# pam2803-boost-driver-17mm-mk-1_1.net
KiCad netlist of a schematic drawn in EAGLE
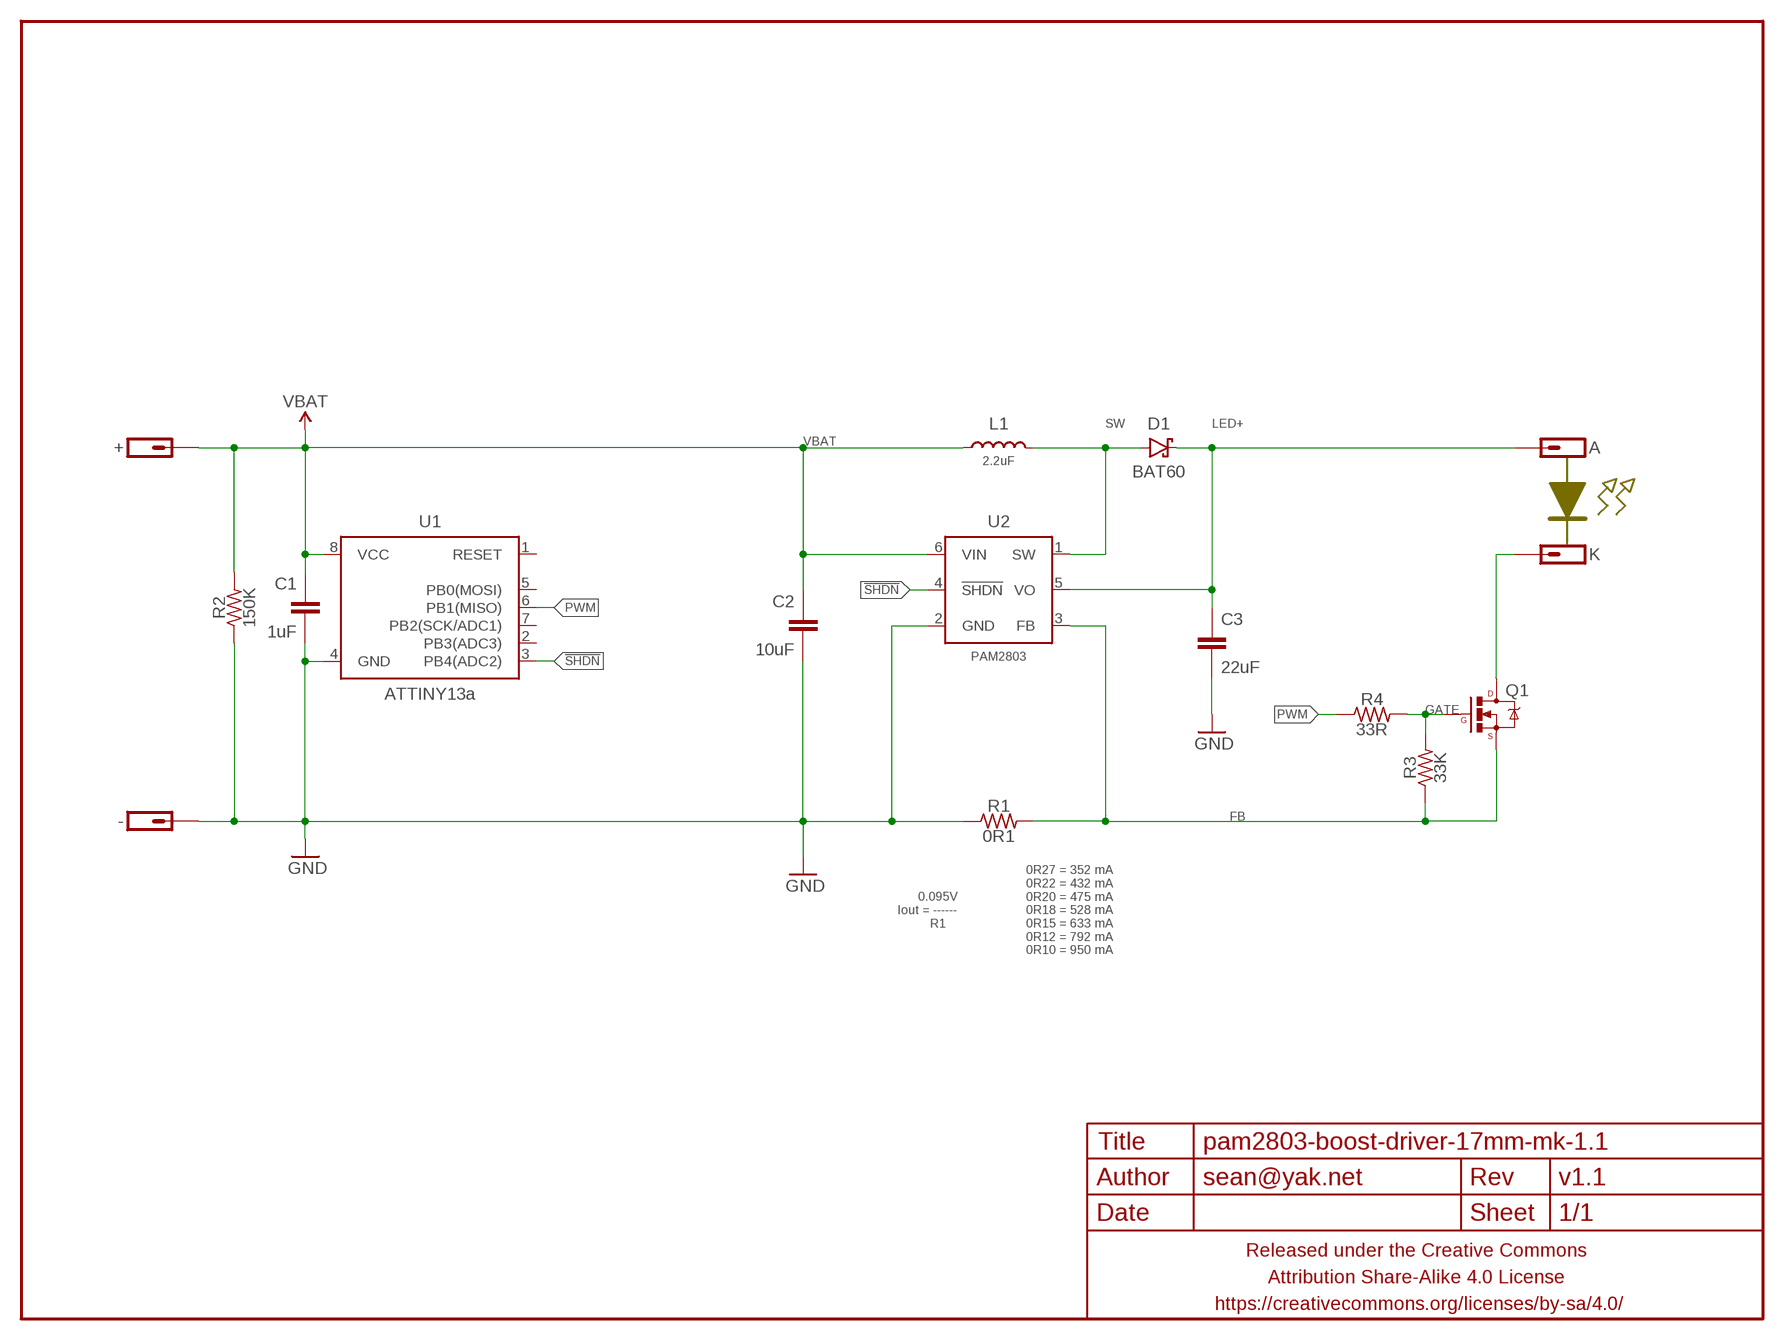
[diagram p0: schematic, sheet 1]

(export (version "E")
  (design (tool "Eeschema 10.0.6"))
  (components
    (comp (ref "+")
      (value "M01PTH-1MM-CIR-NS")
      (footprint "eagle-import:1X01-1MM-CIR-NS")
      (libsource (lib "eagle-import") (part "M01PTH-1MM-CIR-NS"))
    )
    (comp (ref "-")
      (value "M01NOT-A-VIA-NOPE")
      (footprint "eagle-import:1X01_NOSILK_NOSTOP")
      (libsource (lib "eagle-import") (part "M01NOT-A-VIA-NOPE"))
    )
    (comp (ref "A")
      (value "M01PTH-1MM-CIR-NS")
      (footprint "eagle-import:1X01-1MM-CIR-NS")
      (libsource (lib "eagle-import") (part "M01PTH-1MM-CIR-NS"))
    )
    (comp (ref "C1")
      (value "1uF")
      (footprint "eagle-import:C0402")
      (libsource (lib "eagle-import") (part "CAPACITOR-CERAMICC0402"))
    )
    (comp (ref "C2")
      (value "10uF")
      (footprint "eagle-import:C0805-TIGHTER")
      (libsource (lib "eagle-import") (part "CAPACITOR-CERAMICC0805-TIGHTER"))
    )
    (comp (ref "C3")
      (value "22uF")
      (footprint "eagle-import:C0805-TIGHTER")
      (libsource (lib "eagle-import") (part "CAPACITOR-CERAMICC0805-TIGHTER"))
    )
    (comp (ref "D1")
      (value "BAT60")
      (footprint "eagle-import:SOD323-SCHOTTKY")
      (libsource (lib "eagle-import") (part "DIODE-SCHOTTKYSOD323"))
    )
    (comp (ref "FRAME1")
      (value "FRAME-LETTERNO_PACKAGE")
      (footprint "eagle-import:DUMMY")
      (fields (field (name "DESIGNER") "sean@yak.net") (field (name "VERSION") "v1.1"))
      (libsource (lib "eagle-import") (part "FRAME-LETTERNO_PACKAGE"))
    )
    (comp (ref "K")
      (value "M01PTH-1MM-CIR-NS")
      (footprint "eagle-import:1X01-1MM-CIR-NS")
      (libsource (lib "eagle-import") (part "M01PTH-1MM-CIR-NS"))
    )
    (comp (ref "L1")
      (value "2.2uF")
      (footprint "eagle-import:XFL4020")
      (libsource (lib "eagle-import") (part "INDUCTORXFL4020"))
    )
    (comp (ref "Q1")
      (value "MOSFET-NCHANNELIRLML2502")
      (footprint "eagle-import:SOT23")
      (libsource (lib "eagle-import") (part "MOSFET-NCHANNELIRLML2502"))
    )
    (comp (ref "R1")
      (value "0R1")
      (footprint "eagle-import:R0805-TIGHTER")
      (libsource (lib "eagle-import") (part "RESISTORR0805-TIGHTER"))
    )
    (comp (ref "R2")
      (value "150K")
      (footprint "eagle-import:R0603-TIGHTER")
      (libsource (lib "eagle-import") (part "RESISTORR0603-TIGHTER"))
    )
    (comp (ref "R3")
      (value "33K")
      (footprint "eagle-import:R0603-TIGHTER")
      (libsource (lib "eagle-import") (part "RESISTORR0603-TIGHTER"))
    )
    (comp (ref "R4")
      (value "33R")
      (footprint "eagle-import:R0603-TIGHTER")
      (libsource (lib "eagle-import") (part "RESISTORR0603-TIGHTER"))
    )
    (comp (ref "U1")
      (value "ATTINY13a")
      (footprint "eagle-import:SO08-SKINNYPADS")
      (libsource (lib "eagle-import") (part "ATTINY13SOIC-NARROWER"))
    )
    (comp (ref "U2")
      (value "PAM2803")
      (footprint "eagle-import:SOT23-6")
      (libsource (lib "eagle-import") (part "PAM2803SOT23-6"))
    )
  )
  (nets
    (net (code "1") (name "/FB") (class "Default")
      (node (ref "Q1") (pin "2") (pinfunction "S_2") (pintype "passive"))
      (node (ref "R1") (pin "2") (pinfunction "2_2") (pintype "passive"))
      (node (ref "R3") (pin "1") (pinfunction "1_1") (pintype "passive"))
      (node (ref "U2") (pin "3") (pinfunction "FB_3") (pintype "bidirectional"))
    )
    (net (code "2") (name "/GATE") (class "Default")
      (node (ref "Q1") (pin "1") (pinfunction "G_1") (pintype "passive"))
      (node (ref "R3") (pin "2") (pinfunction "2_2") (pintype "passive"))
      (node (ref "R4") (pin "2") (pinfunction "2_2") (pintype "passive"))
    )
    (net (code "3") (name "/LED+") (class "Default")
      (node (ref "A") (pin "1") (pinfunction "1_1") (pintype "passive"))
      (node (ref "C3") (pin "1") (pinfunction "1_1") (pintype "passive"))
      (node (ref "D1") (pin "C") (pinfunction "C_C") (pintype "passive"))
      (node (ref "U2") (pin "5") (pinfunction "VO_5") (pintype "bidirectional"))
    )
    (net (code "4") (name "/SW") (class "Default")
      (node (ref "D1") (pin "A") (pinfunction "A_A") (pintype "passive"))
      (node (ref "L1") (pin "P$1") (pinfunction "1_P$1") (pintype "passive"))
      (node (ref "U2") (pin "1") (pinfunction "SW_1") (pintype "bidirectional"))
    )
    (net (code "5") (name "/~{SHDN}") (class "Default")
      (node (ref "U1") (pin "3") (pinfunction "PB4(ADC2)_3") (pintype "bidirectional"))
      (node (ref "U2") (pin "4") (pinfunction "~{SHDN}_4") (pintype "bidirectional"))
    )
    (net (code "6") (name "GND") (class "Default")
      (node (ref "-") (pin "P$1") (pinfunction "1_P$1") (pintype "passive"))
      (node (ref "C1") (pin "2") (pinfunction "2_2") (pintype "passive"))
      (node (ref "C2") (pin "2") (pinfunction "2_2") (pintype "passive"))
      (node (ref "C3") (pin "2") (pinfunction "2_2") (pintype "passive"))
      (node (ref "R1") (pin "1") (pinfunction "1_1") (pintype "passive"))
      (node (ref "R2") (pin "1") (pinfunction "1_1") (pintype "passive"))
      (node (ref "U1") (pin "4") (pinfunction "GND_4") (pintype "bidirectional"))
      (node (ref "U2") (pin "2") (pinfunction "GND_2") (pintype "bidirectional"))
    )
    (net (code "7") (name "Net-(Q1-D)") (class "Default")
      (node (ref "K") (pin "1") (pinfunction "1_1") (pintype "passive"))
      (node (ref "Q1") (pin "3") (pinfunction "D_3") (pintype "passive"))
    )
    (net (code "8") (name "PWM") (class "Default")
      (node (ref "R4") (pin "1") (pinfunction "1_1") (pintype "passive"))
      (node (ref "U1") (pin "6") (pinfunction "PB1(MISO)_6") (pintype "bidirectional"))
    )
    (net (code "9") (name "VBAT") (class "Default")
      (node (ref "+") (pin "1") (pinfunction "1_1") (pintype "passive"))
      (node (ref "C1") (pin "1") (pinfunction "1_1") (pintype "passive"))
      (node (ref "C2") (pin "1") (pinfunction "1_1") (pintype "passive"))
      (node (ref "L1") (pin "P$2") (pinfunction "2_P$2") (pintype "passive"))
      (node (ref "R2") (pin "2") (pinfunction "2_2") (pintype "passive"))
      (node (ref "U1") (pin "8") (pinfunction "VCC_8") (pintype "bidirectional"))
      (node (ref "U2") (pin "6") (pinfunction "VIN_6") (pintype "bidirectional"))
    )
    (net (code "10") (name "unconnected-(U1-PB0(MOSI)-Pad5)") (class "Default")
      (node (ref "U1") (pin "5") (pinfunction "PB0(MOSI)_5") (pintype "bidirectional"))
    )
    (net (code "11") (name "unconnected-(U1-PB2(SCK{slash}ADC1)-Pad7)") (class "Default")
      (node (ref "U1") (pin "7") (pinfunction "PB2(SCK/ADC1)_7") (pintype "bidirectional"))
    )
    (net (code "12") (name "unconnected-(U1-PB3(ADC3)-Pad2)") (class "Default")
      (node (ref "U1") (pin "2") (pinfunction "PB3(ADC3)_2") (pintype "bidirectional"))
    )
    (net (code "13") (name "unconnected-(U1-RESET-Pad1)") (class "Default")
      (node (ref "U1") (pin "1") (pinfunction "RESET_1") (pintype "bidirectional"))
    )
  )
)
